# RAM.net
KiCad netlist of a schematic drawn in EasyEDA Pro
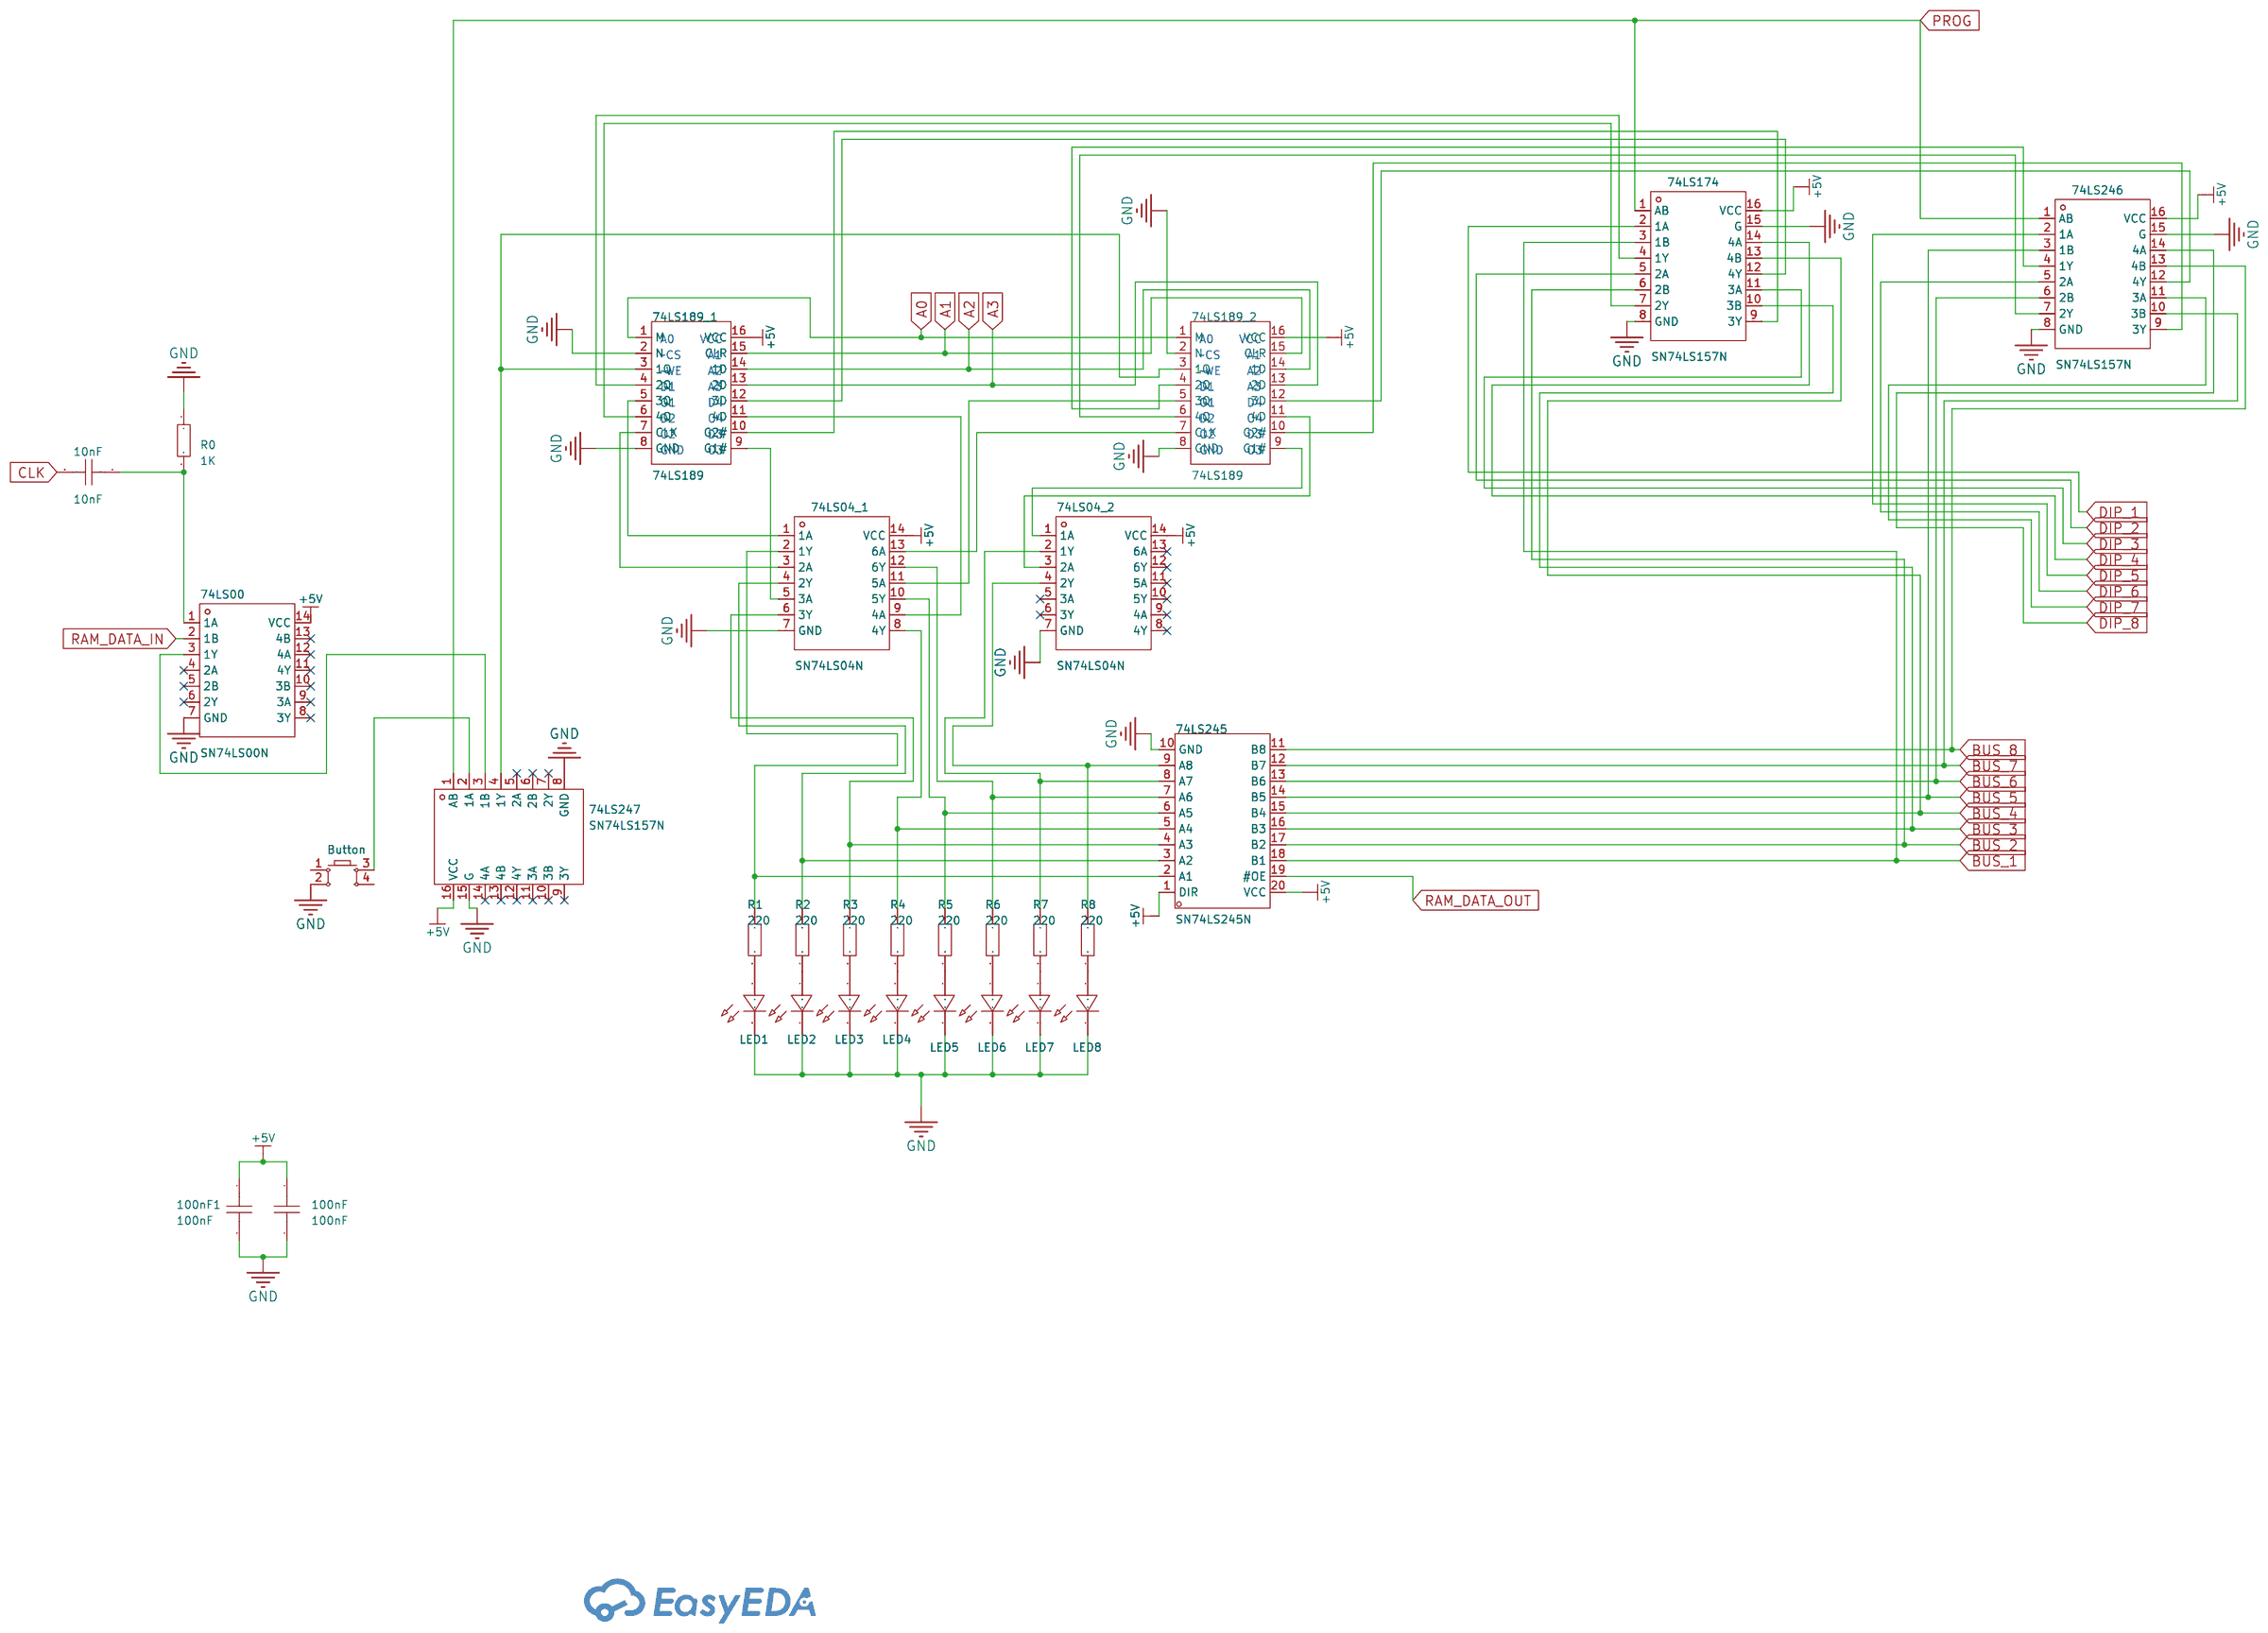
[diagram p0: schematic sheet]

(export (version "E")
  (design (tool "Eeschema 10.0.6"))
  (components
    (comp (ref "10nF")
      (value "10nF")
      (footprint "easyedapro:CAP-TH_L8.5-W5.0-P5.00-D1.2")
      (fields (field (name "Manufacturer Part") "CT4-0805B104K500F3") (field (name "Manufacturer") "FH(风华)"))
      (libsource (lib "easyedapro") (part "CT4-0805B104K500F3"))
    )
    (comp (ref "74LS00")
      (value "SN74LS00N")
      (footprint "easyedapro:PDIP-14_L19.7-W6.6-P2.54-LS8.3-BL")
      (fields (field (name "Manufacturer") "TI(德州仪器)"))
      (libsource (lib "easyedapro") (part "SN74LS00N"))
    )
    (comp (ref "74LS04_1")
      (value "SN74LS04N")
      (footprint "easyedapro:PDIP-14_L19.7-W6.6-P2.54-LS8.3-BL")
      (fields (field (name "Manufacturer") "TI(德州仪器)"))
      (libsource (lib "easyedapro") (part "SN74LS04N"))
    )
    (comp (ref "74LS04_2")
      (value "SN74LS04N")
      (footprint "easyedapro:PDIP-14_L19.7-W6.6-P2.54-LS8.3-BL")
      (fields (field (name "Manufacturer") "TI(德州仪器)"))
      (libsource (lib "easyedapro") (part "SN74LS04N"))
    )
    (comp (ref "74LS174")
      (value "SN74LS157N")
      (footprint "easyedapro:DIP-16_16P-L20.2-W6.6-P2.54-LS7.6-BL")
      (fields (field (name "Manufacturer") "TI(德州仪器)"))
      (libsource (lib "easyedapro") (part "SN74LS157N"))
    )
    (comp (ref "74LS189_1")
      (value "74LS189")
      (footprint "easyedapro:PDIP-16_L19.3-W6.4-P2.54-LS7.94-BL")
      (fields (field (name "Manufacturer Part") "SN74LS173AN") (field (name "Manufacturer") "TI(德州仪器)"))
      (libsource (lib "easyedapro") (part "SN74LS173AN"))
    )
    (comp (ref "74LS189_2")
      (value "74LS189")
      (footprint "easyedapro:PDIP-16_L19.3-W6.4-P2.54-LS7.94-BL")
      (fields (field (name "Manufacturer Part") "SN74LS173AN") (field (name "Manufacturer") "TI(德州仪器)"))
      (libsource (lib "easyedapro") (part "SN74LS173AN"))
    )
    (comp (ref "74LS245")
      (value "SN74LS245N")
      (footprint "easyedapro:DIP-20_L25.5-W10.0-P2.54-LS7.6-BL")
      (fields (field (name "Manufacturer") "TI(德州仪器)"))
      (libsource (lib "easyedapro") (part "SN74LS245N"))
    )
    (comp (ref "74LS246")
      (value "SN74LS157N")
      (footprint "easyedapro:DIP-16_16P-L20.2-W6.6-P2.54-LS7.6-BL")
      (fields (field (name "Manufacturer") "TI(德州仪器)"))
      (libsource (lib "easyedapro") (part "SN74LS157N"))
    )
    (comp (ref "74LS247")
      (value "SN74LS157N")
      (footprint "easyedapro:DIP-16_16P-L20.2-W6.6-P2.54-LS7.6-BL")
      (fields (field (name "Manufacturer") "TI(德州仪器)"))
      (libsource (lib "easyedapro") (part "SN74LS157N"))
    )
    (comp (ref "100nF")
      (value "100nF")
      (footprint "easyedapro:CAP-TH_L8.5-W5.0-P5.00-D1.2")
      (fields (field (name "Manufacturer Part") "CT4-0805B104K500F3") (field (name "Manufacturer") "FH(风华)"))
      (libsource (lib "easyedapro") (part "CT4-0805B104K500F3"))
    )
    (comp (ref "100nF1")
      (value "100nF")
      (footprint "easyedapro:CAP-TH_L8.5-W5.0-P5.00-D1.2")
      (fields (field (name "Manufacturer Part") "CT4-0805B104K500F3") (field (name "Manufacturer") "FH(风华)"))
      (libsource (lib "easyedapro") (part "CT4-0805B104K500F3"))
    )
    (comp (ref "Button")
      (value "~")
      (footprint "easyedapro:SW-TH_4P-L6.0-W6.0-P4.50-LS6.5")
      (libsource (lib "easyedapro") (part "轻触按键"))
    )
    (comp (ref "LED1")
      (value "~")
      (footprint "easyedapro:LED-TH_BD5.8-P2.54-FD")
      (libsource (lib "easyedapro") (part "LED_TH-R"))
    )
    (comp (ref "LED2")
      (value "~")
      (footprint "easyedapro:LED-TH_BD5.8-P2.54-FD")
      (libsource (lib "easyedapro") (part "LED_TH-R"))
    )
    (comp (ref "LED3")
      (value "~")
      (footprint "easyedapro:LED-TH_BD5.8-P2.54-FD")
      (libsource (lib "easyedapro") (part "LED_TH-R"))
    )
    (comp (ref "LED4")
      (value "~")
      (footprint "easyedapro:LED-TH_BD5.8-P2.54-FD")
      (libsource (lib "easyedapro") (part "LED_TH-R"))
    )
    (comp (ref "LED5")
      (value "~")
      (footprint "easyedapro:LED-TH_BD5.8-P2.54-FD")
      (libsource (lib "easyedapro") (part "LED_TH-R"))
    )
    (comp (ref "LED6")
      (value "~")
      (footprint "easyedapro:LED-TH_BD5.8-P2.54-FD")
      (libsource (lib "easyedapro") (part "LED_TH-R"))
    )
    (comp (ref "LED7")
      (value "~")
      (footprint "easyedapro:LED-TH_BD5.8-P2.54-FD")
      (libsource (lib "easyedapro") (part "LED_TH-R"))
    )
    (comp (ref "LED8")
      (value "~")
      (footprint "easyedapro:LED-TH_BD5.8-P2.54-FD")
      (libsource (lib "easyedapro") (part "LED_TH-R"))
    )
    (comp (ref "R0")
      (value "1K")
      (footprint "easyedapro:R_AXIAL-0.4")
      (libsource (lib "easyedapro") (part "Res"))
    )
    (comp (ref "R1")
      (value "220")
      (footprint "easyedapro:R_AXIAL-0.4")
      (libsource (lib "easyedapro") (part "Res"))
    )
    (comp (ref "R2")
      (value "220")
      (footprint "easyedapro:R_AXIAL-0.4")
      (libsource (lib "easyedapro") (part "Res"))
    )
    (comp (ref "R3")
      (value "220")
      (footprint "easyedapro:R_AXIAL-0.4")
      (libsource (lib "easyedapro") (part "Res"))
    )
    (comp (ref "R4")
      (value "220")
      (footprint "easyedapro:R_AXIAL-0.4")
      (libsource (lib "easyedapro") (part "Res"))
    )
    (comp (ref "R5")
      (value "220")
      (footprint "easyedapro:R_AXIAL-0.4")
      (libsource (lib "easyedapro") (part "Res"))
    )
    (comp (ref "R6")
      (value "220")
      (footprint "easyedapro:R_AXIAL-0.4")
      (libsource (lib "easyedapro") (part "Res"))
    )
    (comp (ref "R7")
      (value "220")
      (footprint "easyedapro:R_AXIAL-0.4")
      (libsource (lib "easyedapro") (part "Res"))
    )
    (comp (ref "R8")
      (value "220")
      (footprint "easyedapro:R_AXIAL-0.4")
      (libsource (lib "easyedapro") (part "Res"))
    )
  )
  (nets
    (net (code "1") (name "+5V") (class "Default")
      (node (ref "100nF") (pin "1") (pinfunction "1_1") (pintype "unspecified"))
      (node (ref "100nF1") (pin "1") (pinfunction "1_1") (pintype "unspecified"))
      (node (ref "74LS00") (pin "14") (pinfunction "VCC_14") (pintype "unspecified"))
      (node (ref "74LS04_1") (pin "14") (pinfunction "VCC_14") (pintype "unspecified"))
      (node (ref "74LS04_2") (pin "14") (pinfunction "VCC_14") (pintype "unspecified"))
      (node (ref "74LS174") (pin "16") (pinfunction "VCC_16") (pintype "unspecified"))
      (node (ref "74LS189_1") (pin "16") (pinfunction "VCC_16") (pintype "unspecified"))
      (node (ref "74LS189_2") (pin "16") (pinfunction "VCC_16") (pintype "unspecified"))
      (node (ref "74LS245") (pin "1") (pinfunction "DIR_1") (pintype "input"))
      (node (ref "74LS245") (pin "20") (pinfunction "VCC_20") (pintype "input"))
      (node (ref "74LS246") (pin "16") (pinfunction "VCC_16") (pintype "unspecified"))
      (node (ref "74LS247") (pin "16") (pinfunction "VCC_16") (pintype "unspecified"))
    )
    (net (code "2") (name "A0") (class "Default")
      (node (ref "74LS189_1") (pin "1") (pinfunction "M_1") (pintype "unspecified"))
      (node (ref "74LS189_2") (pin "1") (pinfunction "M_1") (pintype "unspecified"))
    )
    (net (code "3") (name "A1") (class "Default")
      (node (ref "74LS189_1") (pin "15") (pinfunction "CLR_15") (pintype "unspecified"))
      (node (ref "74LS189_2") (pin "15") (pinfunction "CLR_15") (pintype "unspecified"))
    )
    (net (code "4") (name "A2") (class "Default")
      (node (ref "74LS189_1") (pin "14") (pinfunction "1D_14") (pintype "unspecified"))
      (node (ref "74LS189_2") (pin "14") (pinfunction "1D_14") (pintype "unspecified"))
    )
    (net (code "5") (name "A3") (class "Default")
      (node (ref "74LS189_1") (pin "13") (pinfunction "2D_13") (pintype "unspecified"))
      (node (ref "74LS189_2") (pin "13") (pinfunction "2D_13") (pintype "unspecified"))
    )
    (net (code "6") (name "BUS_1") (class "Default")
      (node (ref "74LS174") (pin "3") (pinfunction "1B_3") (pintype "unspecified"))
      (node (ref "74LS245") (pin "18") (pinfunction "B1_18") (pintype "input"))
    )
    (net (code "7") (name "BUS_2") (class "Default")
      (node (ref "74LS174") (pin "6") (pinfunction "2B_6") (pintype "unspecified"))
      (node (ref "74LS245") (pin "17") (pinfunction "B2_17") (pintype "input"))
    )
    (net (code "8") (name "BUS_3") (class "Default")
      (node (ref "74LS174") (pin "10") (pinfunction "3B_10") (pintype "unspecified"))
      (node (ref "74LS245") (pin "16") (pinfunction "B3_16") (pintype "input"))
    )
    (net (code "9") (name "BUS_4") (class "Default")
      (node (ref "74LS174") (pin "13") (pinfunction "4B_13") (pintype "unspecified"))
      (node (ref "74LS245") (pin "15") (pinfunction "B4_15") (pintype "input"))
    )
    (net (code "10") (name "BUS_5") (class "Default")
      (node (ref "74LS245") (pin "14") (pinfunction "B5_14") (pintype "input"))
      (node (ref "74LS246") (pin "3") (pinfunction "1B_3") (pintype "unspecified"))
    )
    (net (code "11") (name "BUS_6") (class "Default")
      (node (ref "74LS245") (pin "13") (pinfunction "B6_13") (pintype "input"))
      (node (ref "74LS246") (pin "6") (pinfunction "2B_6") (pintype "unspecified"))
    )
    (net (code "12") (name "BUS_7") (class "Default")
      (node (ref "74LS245") (pin "12") (pinfunction "B7_12") (pintype "input"))
      (node (ref "74LS246") (pin "10") (pinfunction "3B_10") (pintype "unspecified"))
    )
    (net (code "13") (name "BUS_8") (class "Default")
      (node (ref "74LS245") (pin "11") (pinfunction "B8_11") (pintype "input"))
      (node (ref "74LS246") (pin "13") (pinfunction "4B_13") (pintype "unspecified"))
    )
    (net (code "14") (name "CLK") (class "Default")
      (node (ref "10nF") (pin "2") (pinfunction "2_2") (pintype "unspecified"))
    )
    (net (code "15") (name "DIP_1") (class "Default")
      (node (ref "74LS174") (pin "2") (pinfunction "1A_2") (pintype "unspecified"))
    )
    (net (code "16") (name "DIP_2") (class "Default")
      (node (ref "74LS174") (pin "5") (pinfunction "2A_5") (pintype "unspecified"))
    )
    (net (code "17") (name "DIP_3") (class "Default")
      (node (ref "74LS174") (pin "11") (pinfunction "3A_11") (pintype "unspecified"))
    )
    (net (code "18") (name "DIP_4") (class "Default")
      (node (ref "74LS174") (pin "14") (pinfunction "4A_14") (pintype "unspecified"))
    )
    (net (code "19") (name "DIP_5") (class "Default")
      (node (ref "74LS246") (pin "2") (pinfunction "1A_2") (pintype "unspecified"))
    )
    (net (code "20") (name "DIP_6") (class "Default")
      (node (ref "74LS246") (pin "5") (pinfunction "2A_5") (pintype "unspecified"))
    )
    (net (code "21") (name "DIP_7") (class "Default")
      (node (ref "74LS246") (pin "11") (pinfunction "3A_11") (pintype "unspecified"))
    )
    (net (code "22") (name "DIP_8") (class "Default")
      (node (ref "74LS246") (pin "14") (pinfunction "4A_14") (pintype "unspecified"))
    )
    (net (code "23") (name "GND") (class "Default")
      (node (ref "100nF") (pin "2") (pinfunction "2_2") (pintype "unspecified"))
      (node (ref "100nF1") (pin "2") (pinfunction "2_2") (pintype "unspecified"))
      (node (ref "74LS00") (pin "7") (pinfunction "GND_7") (pintype "unspecified"))
      (node (ref "74LS04_1") (pin "7") (pinfunction "GND_7") (pintype "unspecified"))
      (node (ref "74LS04_2") (pin "7") (pinfunction "GND_7") (pintype "unspecified"))
      (node (ref "74LS174") (pin "15") (pinfunction "G_15") (pintype "unspecified"))
      (node (ref "74LS174") (pin "8") (pinfunction "GND_8") (pintype "unspecified"))
      (node (ref "74LS189_1") (pin "2") (pinfunction "N_2") (pintype "unspecified"))
      (node (ref "74LS189_1") (pin "8") (pinfunction "GND_8") (pintype "unspecified"))
      (node (ref "74LS189_2") (pin "2") (pinfunction "N_2") (pintype "unspecified"))
      (node (ref "74LS189_2") (pin "8") (pinfunction "GND_8") (pintype "unspecified"))
      (node (ref "74LS245") (pin "10") (pinfunction "GND_10") (pintype "input"))
      (node (ref "74LS246") (pin "15") (pinfunction "G_15") (pintype "unspecified"))
      (node (ref "74LS246") (pin "8") (pinfunction "GND_8") (pintype "unspecified"))
      (node (ref "74LS247") (pin "15") (pinfunction "G_15") (pintype "unspecified"))
      (node (ref "74LS247") (pin "8") (pinfunction "GND_8") (pintype "unspecified"))
      (node (ref "Button") (pin "2") (pinfunction "2_2") (pintype "input"))
      (node (ref "LED1") (pin "2") (pinfunction "A_2") (pintype "input"))
      (node (ref "LED2") (pin "2") (pinfunction "A_2") (pintype "input"))
      (node (ref "LED3") (pin "2") (pinfunction "A_2") (pintype "input"))
      (node (ref "LED4") (pin "2") (pinfunction "A_2") (pintype "input"))
      (node (ref "LED5") (pin "2") (pinfunction "A_2") (pintype "input"))
      (node (ref "LED6") (pin "2") (pinfunction "A_2") (pintype "input"))
      (node (ref "LED7") (pin "2") (pinfunction "A_2") (pintype "input"))
      (node (ref "LED8") (pin "2") (pinfunction "A_2") (pintype "input"))
      (node (ref "R0") (pin "1") (pinfunction "1_1") (pintype "input"))
    )
    (net (code "24") (name "Net-(74LS00-1A)") (class "Default")
      (node (ref "10nF") (pin "1") (pinfunction "1_1") (pintype "unspecified"))
      (node (ref "74LS00") (pin "1") (pinfunction "1A_1") (pintype "unspecified"))
      (node (ref "R0") (pin "2") (pinfunction "2_2") (pintype "input"))
    )
    (net (code "25") (name "Net-(74LS00-1Y)") (class "Default")
      (node (ref "74LS00") (pin "3") (pinfunction "1Y_3") (pintype "unspecified"))
      (node (ref "74LS247") (pin "3") (pinfunction "1B_3") (pintype "unspecified"))
    )
    (net (code "26") (name "Net-(74LS04_1-1A)") (class "Default")
      (node (ref "74LS04_1") (pin "1") (pinfunction "1A_1") (pintype "unspecified"))
      (node (ref "74LS189_1") (pin "5") (pinfunction "3Q_5") (pintype "unspecified"))
    )
    (net (code "27") (name "Net-(74LS04_1-1Y)") (class "Default")
      (node (ref "74LS04_1") (pin "2") (pinfunction "1Y_2") (pintype "unspecified"))
      (node (ref "74LS245") (pin "2") (pinfunction "A1_2") (pintype "input"))
      (node (ref "R1") (pin "1") (pinfunction "1_1") (pintype "input"))
    )
    (net (code "28") (name "Net-(74LS04_1-2A)") (class "Default")
      (node (ref "74LS04_1") (pin "3") (pinfunction "2A_3") (pintype "unspecified"))
      (node (ref "74LS189_1") (pin "7") (pinfunction "CLK_7") (pintype "unspecified"))
    )
    (net (code "29") (name "Net-(74LS04_1-2Y)") (class "Default")
      (node (ref "74LS04_1") (pin "4") (pinfunction "2Y_4") (pintype "unspecified"))
      (node (ref "74LS245") (pin "3") (pinfunction "A2_3") (pintype "input"))
      (node (ref "R2") (pin "1") (pinfunction "1_1") (pintype "input"))
    )
    (net (code "30") (name "Net-(74LS04_1-3A)") (class "Default")
      (node (ref "74LS04_1") (pin "5") (pinfunction "3A_5") (pintype "unspecified"))
      (node (ref "74LS189_1") (pin "9") (pinfunction "G1#_9") (pintype "unspecified"))
    )
    (net (code "31") (name "Net-(74LS04_1-3Y)") (class "Default")
      (node (ref "74LS04_1") (pin "6") (pinfunction "3Y_6") (pintype "unspecified"))
      (node (ref "74LS245") (pin "4") (pinfunction "A3_4") (pintype "input"))
      (node (ref "R3") (pin "1") (pinfunction "1_1") (pintype "input"))
    )
    (net (code "32") (name "Net-(74LS04_1-4A)") (class "Default")
      (node (ref "74LS04_1") (pin "9") (pinfunction "4A_9") (pintype "unspecified"))
      (node (ref "74LS189_1") (pin "11") (pinfunction "4D_11") (pintype "unspecified"))
    )
    (net (code "33") (name "Net-(74LS04_1-4Y)") (class "Default")
      (node (ref "74LS04_1") (pin "8") (pinfunction "4Y_8") (pintype "unspecified"))
      (node (ref "74LS245") (pin "5") (pinfunction "A4_5") (pintype "input"))
      (node (ref "R4") (pin "1") (pinfunction "1_1") (pintype "input"))
    )
    (net (code "34") (name "Net-(74LS04_1-5A)") (class "Default")
      (node (ref "74LS04_1") (pin "11") (pinfunction "5A_11") (pintype "unspecified"))
      (node (ref "74LS189_2") (pin "5") (pinfunction "3Q_5") (pintype "unspecified"))
    )
    (net (code "35") (name "Net-(74LS04_1-5Y)") (class "Default")
      (node (ref "74LS04_1") (pin "10") (pinfunction "5Y_10") (pintype "unspecified"))
      (node (ref "74LS245") (pin "6") (pinfunction "A5_6") (pintype "input"))
      (node (ref "R5") (pin "1") (pinfunction "1_1") (pintype "input"))
    )
    (net (code "36") (name "Net-(74LS04_1-6A)") (class "Default")
      (node (ref "74LS04_1") (pin "13") (pinfunction "6A_13") (pintype "unspecified"))
      (node (ref "74LS189_2") (pin "7") (pinfunction "CLK_7") (pintype "unspecified"))
    )
    (net (code "37") (name "Net-(74LS04_1-6Y)") (class "Default")
      (node (ref "74LS04_1") (pin "12") (pinfunction "6Y_12") (pintype "unspecified"))
      (node (ref "74LS245") (pin "7") (pinfunction "A6_7") (pintype "input"))
      (node (ref "R6") (pin "1") (pinfunction "1_1") (pintype "input"))
    )
    (net (code "38") (name "Net-(74LS04_2-1A)") (class "Default")
      (node (ref "74LS04_2") (pin "1") (pinfunction "1A_1") (pintype "unspecified"))
      (node (ref "74LS189_2") (pin "9") (pinfunction "G1#_9") (pintype "unspecified"))
    )
    (net (code "39") (name "Net-(74LS04_2-1Y)") (class "Default")
      (node (ref "74LS04_2") (pin "2") (pinfunction "1Y_2") (pintype "unspecified"))
      (node (ref "74LS245") (pin "8") (pinfunction "A7_8") (pintype "input"))
      (node (ref "R7") (pin "1") (pinfunction "1_1") (pintype "input"))
    )
    (net (code "40") (name "Net-(74LS04_2-2A)") (class "Default")
      (node (ref "74LS04_2") (pin "3") (pinfunction "2A_3") (pintype "unspecified"))
      (node (ref "74LS189_2") (pin "11") (pinfunction "4D_11") (pintype "unspecified"))
    )
    (net (code "41") (name "Net-(74LS04_2-2Y)") (class "Default")
      (node (ref "74LS04_2") (pin "4") (pinfunction "2Y_4") (pintype "unspecified"))
      (node (ref "74LS245") (pin "9") (pinfunction "A8_9") (pintype "input"))
      (node (ref "R8") (pin "1") (pinfunction "1_1") (pintype "input"))
    )
    (net (code "42") (name "Net-(74LS174-1Y)") (class "Default")
      (node (ref "74LS174") (pin "4") (pinfunction "1Y_4") (pintype "unspecified"))
      (node (ref "74LS189_1") (pin "4") (pinfunction "2Q_4") (pintype "unspecified"))
    )
    (net (code "43") (name "Net-(74LS174-2Y)") (class "Default")
      (node (ref "74LS174") (pin "7") (pinfunction "2Y_7") (pintype "unspecified"))
      (node (ref "74LS189_1") (pin "6") (pinfunction "4Q_6") (pintype "unspecified"))
    )
    (net (code "44") (name "Net-(74LS174-3Y)") (class "Default")
      (node (ref "74LS174") (pin "9") (pinfunction "3Y_9") (pintype "unspecified"))
      (node (ref "74LS189_1") (pin "10") (pinfunction "G2#_10") (pintype "unspecified"))
    )
    (net (code "45") (name "Net-(74LS174-4Y)") (class "Default")
      (node (ref "74LS174") (pin "12") (pinfunction "4Y_12") (pintype "unspecified"))
      (node (ref "74LS189_1") (pin "12") (pinfunction "3D_12") (pintype "unspecified"))
    )
    (net (code "46") (name "Net-(74LS189_1-1Q)") (class "Default")
      (node (ref "74LS189_1") (pin "3") (pinfunction "1Q_3") (pintype "unspecified"))
      (node (ref "74LS189_2") (pin "3") (pinfunction "1Q_3") (pintype "unspecified"))
      (node (ref "74LS247") (pin "4") (pinfunction "1Y_4") (pintype "unspecified"))
    )
    (net (code "47") (name "Net-(74LS189_2-2Q)") (class "Default")
      (node (ref "74LS189_2") (pin "4") (pinfunction "2Q_4") (pintype "unspecified"))
      (node (ref "74LS246") (pin "4") (pinfunction "1Y_4") (pintype "unspecified"))
    )
    (net (code "48") (name "Net-(74LS189_2-3D)") (class "Default")
      (node (ref "74LS189_2") (pin "12") (pinfunction "3D_12") (pintype "unspecified"))
      (node (ref "74LS246") (pin "12") (pinfunction "4Y_12") (pintype "unspecified"))
    )
    (net (code "49") (name "Net-(74LS189_2-4Q)") (class "Default")
      (node (ref "74LS189_2") (pin "6") (pinfunction "4Q_6") (pintype "unspecified"))
      (node (ref "74LS246") (pin "7") (pinfunction "2Y_7") (pintype "unspecified"))
    )
    (net (code "50") (name "Net-(74LS189_2-G2#)") (class "Default")
      (node (ref "74LS189_2") (pin "10") (pinfunction "G2#_10") (pintype "unspecified"))
      (node (ref "74LS246") (pin "9") (pinfunction "3Y_9") (pintype "unspecified"))
    )
    (net (code "51") (name "Net-(74LS247-1A)") (class "Default")
      (node (ref "74LS247") (pin "2") (pinfunction "1A_2") (pintype "unspecified"))
      (node (ref "Button") (pin "3") (pinfunction "3_3") (pintype "input"))
    )
    (net (code "52") (name "Net-(LED1-C)") (class "Default")
      (node (ref "LED1") (pin "1") (pinfunction "C_1") (pintype "input"))
      (node (ref "R1") (pin "2") (pinfunction "2_2") (pintype "input"))
    )
    (net (code "53") (name "Net-(LED2-C)") (class "Default")
      (node (ref "LED2") (pin "1") (pinfunction "C_1") (pintype "input"))
      (node (ref "R2") (pin "2") (pinfunction "2_2") (pintype "input"))
    )
    (net (code "54") (name "Net-(LED3-C)") (class "Default")
      (node (ref "LED3") (pin "1") (pinfunction "C_1") (pintype "input"))
      (node (ref "R3") (pin "2") (pinfunction "2_2") (pintype "input"))
    )
    (net (code "55") (name "Net-(LED4-C)") (class "Default")
      (node (ref "LED4") (pin "1") (pinfunction "C_1") (pintype "input"))
      (node (ref "R4") (pin "2") (pinfunction "2_2") (pintype "input"))
    )
    (net (code "56") (name "Net-(LED5-C)") (class "Default")
      (node (ref "LED5") (pin "1") (pinfunction "C_1") (pintype "input"))
      (node (ref "R5") (pin "2") (pinfunction "2_2") (pintype "input"))
    )
    (net (code "57") (name "Net-(LED6-C)") (class "Default")
      (node (ref "LED6") (pin "1") (pinfunction "C_1") (pintype "input"))
      (node (ref "R6") (pin "2") (pinfunction "2_2") (pintype "input"))
    )
    (net (code "58") (name "Net-(LED7-C)") (class "Default")
      (node (ref "LED7") (pin "1") (pinfunction "C_1") (pintype "input"))
      (node (ref "R7") (pin "2") (pinfunction "2_2") (pintype "input"))
    )
    (net (code "59") (name "Net-(LED8-C)") (class "Default")
      (node (ref "LED8") (pin "1") (pinfunction "C_1") (pintype "input"))
      (node (ref "R8") (pin "2") (pinfunction "2_2") (pintype "input"))
    )
    (net (code "60") (name "PROG") (class "Default")
      (node (ref "74LS174") (pin "1") (pinfunction "AB_1") (pintype "unspecified"))
      (node (ref "74LS246") (pin "1") (pinfunction "AB_1") (pintype "unspecified"))
      (node (ref "74LS247") (pin "1") (pinfunction "AB_1") (pintype "unspecified"))
    )
    (net (code "61") (name "RAM_DATA_IN") (class "Default")
      (node (ref "74LS00") (pin "2") (pinfunction "1B_2") (pintype "unspecified"))
    )
    (net (code "62") (name "RAM_DATA_OUT") (class "Default")
      (node (ref "74LS245") (pin "19") (pinfunction "#OE_19") (pintype "input"))
    )
    (net (code "63") (name "unconnected-(74LS00-2A-Pad4)") (class "Default")
      (node (ref "74LS00") (pin "4") (pinfunction "2A_4") (pintype "unspecified+no_connect"))
    )
    (net (code "64") (name "unconnected-(74LS00-2B-Pad5)") (class "Default")
      (node (ref "74LS00") (pin "5") (pinfunction "2B_5") (pintype "unspecified+no_connect"))
    )
    (net (code "65") (name "unconnected-(74LS00-2Y-Pad6)") (class "Default")
      (node (ref "74LS00") (pin "6") (pinfunction "2Y_6") (pintype "unspecified+no_connect"))
    )
    (net (code "66") (name "unconnected-(74LS00-3A-Pad9)") (class "Default")
      (node (ref "74LS00") (pin "9") (pinfunction "3A_9") (pintype "unspecified+no_connect"))
    )
    (net (code "67") (name "unconnected-(74LS00-3B-Pad10)") (class "Default")
      (node (ref "74LS00") (pin "10") (pinfunction "3B_10") (pintype "unspecified+no_connect"))
    )
    (net (code "68") (name "unconnected-(74LS00-3Y-Pad8)") (class "Default")
      (node (ref "74LS00") (pin "8") (pinfunction "3Y_8") (pintype "unspecified+no_connect"))
    )
    (net (code "69") (name "unconnected-(74LS00-4A-Pad12)") (class "Default")
      (node (ref "74LS00") (pin "12") (pinfunction "4A_12") (pintype "unspecified+no_connect"))
    )
    (net (code "70") (name "unconnected-(74LS00-4B-Pad13)") (class "Default")
      (node (ref "74LS00") (pin "13") (pinfunction "4B_13") (pintype "unspecified+no_connect"))
    )
    (net (code "71") (name "unconnected-(74LS00-4Y-Pad11)") (class "Default")
      (node (ref "74LS00") (pin "11") (pinfunction "4Y_11") (pintype "unspecified+no_connect"))
    )
    (net (code "72") (name "unconnected-(74LS04_2-3A-Pad5)") (class "Default")
      (node (ref "74LS04_2") (pin "5") (pinfunction "3A_5") (pintype "unspecified+no_connect"))
    )
    (net (code "73") (name "unconnected-(74LS04_2-3Y-Pad6)") (class "Default")
      (node (ref "74LS04_2") (pin "6") (pinfunction "3Y_6") (pintype "unspecified+no_connect"))
    )
    (net (code "74") (name "unconnected-(74LS04_2-4A-Pad9)") (class "Default")
      (node (ref "74LS04_2") (pin "9") (pinfunction "4A_9") (pintype "unspecified+no_connect"))
    )
    (net (code "75") (name "unconnected-(74LS04_2-4Y-Pad8)") (class "Default")
      (node (ref "74LS04_2") (pin "8") (pinfunction "4Y_8") (pintype "unspecified+no_connect"))
    )
    (net (code "76") (name "unconnected-(74LS04_2-5A-Pad11)") (class "Default")
      (node (ref "74LS04_2") (pin "11") (pinfunction "5A_11") (pintype "unspecified+no_connect"))
    )
    (net (code "77") (name "unconnected-(74LS04_2-5Y-Pad10)") (class "Default")
      (node (ref "74LS04_2") (pin "10") (pinfunction "5Y_10") (pintype "unspecified+no_connect"))
    )
    (net (code "78") (name "unconnected-(74LS04_2-6A-Pad13)") (class "Default")
      (node (ref "74LS04_2") (pin "13") (pinfunction "6A_13") (pintype "unspecified+no_connect"))
    )
    (net (code "79") (name "unconnected-(74LS04_2-6Y-Pad12)") (class "Default")
      (node (ref "74LS04_2") (pin "12") (pinfunction "6Y_12") (pintype "unspecified+no_connect"))
    )
    (net (code "80") (name "unconnected-(74LS247-2A-Pad5)") (class "Default")
      (node (ref "74LS247") (pin "5") (pinfunction "2A_5") (pintype "unspecified+no_connect"))
    )
    (net (code "81") (name "unconnected-(74LS247-2B-Pad6)") (class "Default")
      (node (ref "74LS247") (pin "6") (pinfunction "2B_6") (pintype "unspecified+no_connect"))
    )
    (net (code "82") (name "unconnected-(74LS247-2Y-Pad7)") (class "Default")
      (node (ref "74LS247") (pin "7") (pinfunction "2Y_7") (pintype "unspecified+no_connect"))
    )
    (net (code "83") (name "unconnected-(74LS247-3A-Pad11)") (class "Default")
      (node (ref "74LS247") (pin "11") (pinfunction "3A_11") (pintype "unspecified+no_connect"))
    )
    (net (code "84") (name "unconnected-(74LS247-3B-Pad10)") (class "Default")
      (node (ref "74LS247") (pin "10") (pinfunction "3B_10") (pintype "unspecified+no_connect"))
    )
    (net (code "85") (name "unconnected-(74LS247-3Y-Pad9)") (class "Default")
      (node (ref "74LS247") (pin "9") (pinfunction "3Y_9") (pintype "unspecified+no_connect"))
    )
    (net (code "86") (name "unconnected-(74LS247-4A-Pad14)") (class "Default")
      (node (ref "74LS247") (pin "14") (pinfunction "4A_14") (pintype "unspecified+no_connect"))
    )
    (net (code "87") (name "unconnected-(74LS247-4B-Pad13)") (class "Default")
      (node (ref "74LS247") (pin "13") (pinfunction "4B_13") (pintype "unspecified+no_connect"))
    )
    (net (code "88") (name "unconnected-(74LS247-4Y-Pad12)") (class "Default")
      (node (ref "74LS247") (pin "12") (pinfunction "4Y_12") (pintype "unspecified+no_connect"))
    )
    (net (code "89") (name "unconnected-(Button-Pad1)") (class "Default")
      (node (ref "Button") (pin "1") (pinfunction "1_1") (pintype "input"))
    )
    (net (code "90") (name "unconnected-(Button-Pad4)") (class "Default")
      (node (ref "Button") (pin "4") (pinfunction "4_4") (pintype "input"))
    )
  )
)
